# cpu.net
KiCad netlist of a schematic drawn in Altium Designer
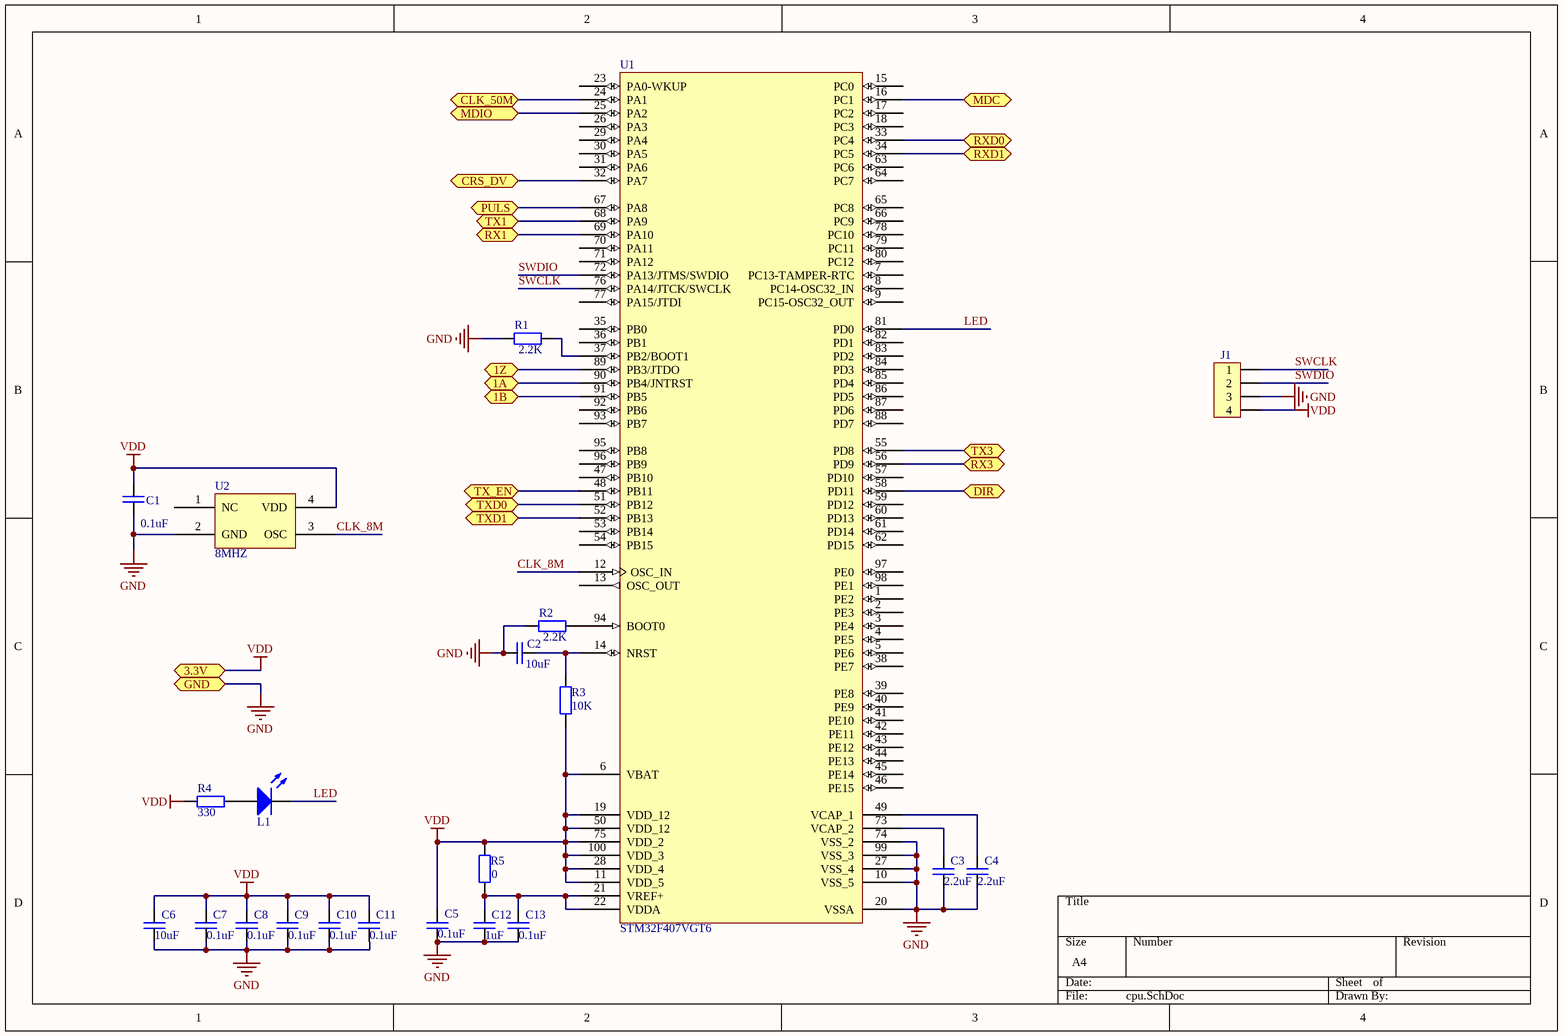
[diagram p0: cpu.SchDoc]

(export (version "E")
  (design (tool "Eeschema 10.0.6"))
  (components
    (comp (ref "C1")
      (value "0.1uF")
      (footprint "CAP-0805")
      (fields (field (name "Comment") "CAP"))
      (libsource (lib "Schlib1") (part "CAP"))
    )
    (comp (ref "C2")
      (value "10uF")
      (footprint "CAP-0805")
      (fields (field (name "Comment") "CAP"))
      (libsource (lib "Schlib1") (part "CAP"))
    )
    (comp (ref "C3")
      (value "2.2uF")
      (footprint "CAP-0805")
      (fields (field (name "Comment") "CAP"))
      (libsource (lib "Schlib1") (part "CAP"))
    )
    (comp (ref "C4")
      (value "2.2uF")
      (footprint "CAP-0805")
      (fields (field (name "Comment") "CAP"))
      (libsource (lib "Schlib1") (part "CAP"))
    )
    (comp (ref "C5")
      (value "0.1uF")
      (footprint "CAP-0805")
      (fields (field (name "Comment") "CAP"))
      (libsource (lib "Schlib1") (part "CAP"))
    )
    (comp (ref "C6")
      (value "10uF")
      (footprint "CAP-0805")
      (fields (field (name "Comment") "CAP"))
      (libsource (lib "Schlib1") (part "CAP"))
    )
    (comp (ref "C7")
      (value "0.1uF")
      (footprint "CAP-0805")
      (fields (field (name "Comment") "CAP"))
      (libsource (lib "Schlib1") (part "CAP"))
    )
    (comp (ref "C8")
      (value "0.1uF")
      (footprint "CAP-0805")
      (fields (field (name "Comment") "CAP"))
      (libsource (lib "Schlib1") (part "CAP"))
    )
    (comp (ref "C9")
      (value "0.1uF")
      (footprint "CAP-0805")
      (fields (field (name "Comment") "CAP"))
      (libsource (lib "Schlib1") (part "CAP"))
    )
    (comp (ref "C10")
      (value "0.1uF")
      (footprint "CAP-0805")
      (fields (field (name "Comment") "CAP"))
      (libsource (lib "Schlib1") (part "CAP"))
    )
    (comp (ref "C11")
      (value "0.1uF")
      (footprint "CAP-0805")
      (fields (field (name "Comment") "CAP"))
      (libsource (lib "Schlib1") (part "CAP"))
    )
    (comp (ref "C12")
      (value "1uF")
      (footprint "CAP-0805")
      (fields (field (name "Comment") "CAP"))
      (libsource (lib "Schlib1") (part "CAP"))
    )
    (comp (ref "C13")
      (value "0.1uF")
      (footprint "CAP-0805")
      (fields (field (name "Comment") "CAP"))
      (libsource (lib "Schlib1") (part "CAP"))
    )
    (comp (ref "J1") (value "HDR1*4") (footprint "HDR1*4") (libsource (lib "Schlib1") (part "HDR1*4")))
    (comp (ref "L1") (value "LED") (footprint "LED-0805") (libsource (lib "Schlib1") (part "LED")))
    (comp (ref "R1")
      (value "2.2K")
      (footprint "RES-0805")
      (fields (field (name "Comment") "RES"))
      (libsource (lib "Schlib1") (part "RES"))
    )
    (comp (ref "R2")
      (value "2.2K")
      (footprint "RES-0805")
      (fields (field (name "Comment") "RES"))
      (libsource (lib "Schlib1") (part "RES"))
    )
    (comp (ref "R3")
      (value "10K")
      (footprint "RES-0805")
      (fields (field (name "Comment") "RES"))
      (libsource (lib "") (part "RES_2"))
    )
    (comp (ref "R4")
      (value "330")
      (footprint "RES-0805")
      (fields (field (name "Comment") "RES"))
      (libsource (lib "") (part "RES_3"))
    )
    (comp (ref "R5")
      (value "0")
      (footprint "RES-0805")
      (fields (field (name "Comment") "RES"))
      (libsource (lib "") (part "RES_1"))
    )
    (comp (ref "U1")
      (value "STM32F407VGT6")
      (footprint "STM32-LQFP100")
      (libsource (lib "Schlib1") (part "STM32F407VGT6"))
    )
    (comp (ref "U2") (value "8MHZ") (footprint "OSC_S") (libsource (lib "Schlib1") (part "OSC")))
  )
  (nets
    (net (code "1") (name "/1A") (class "Default")
      (node (ref "U1") (pin "90") (pinfunction "PB4/JNTRST_90") (pintype "bidirectional"))
    )
    (net (code "2") (name "/1B") (class "Default")
      (node (ref "U1") (pin "91") (pinfunction "PB5_91") (pintype "bidirectional"))
    )
    (net (code "3") (name "/1Z") (class "Default")
      (node (ref "U1") (pin "89") (pinfunction "PB3/JTDO_89") (pintype "bidirectional"))
    )
    (net (code "4") (name "/CLK_8M") (class "Default")
      (node (ref "U1") (pin "12") (pinfunction "OSC_IN_12") (pintype "input"))
      (node (ref "U2") (pin "3") (pinfunction "OSC_3") (pintype "passive"))
    )
    (net (code "5") (name "/CLK_50M") (class "Default")
      (node (ref "U1") (pin "24") (pinfunction "PA1_24") (pintype "bidirectional"))
    )
    (net (code "6") (name "/CRS_DV") (class "Default")
      (node (ref "U1") (pin "32") (pinfunction "PA7_32") (pintype "bidirectional"))
    )
    (net (code "7") (name "/DIR") (class "Default")
      (node (ref "U1") (pin "58") (pinfunction "PD11_58") (pintype "bidirectional"))
    )
    (net (code "8") (name "/LED") (class "Default")
      (node (ref "L1") (pin "2") (pintype "passive"))
      (node (ref "U1") (pin "81") (pinfunction "PD0_81") (pintype "bidirectional"))
    )
    (net (code "9") (name "/MDC") (class "Default")
      (node (ref "U1") (pin "16") (pinfunction "PC1_16") (pintype "bidirectional"))
    )
    (net (code "10") (name "/MDIO") (class "Default")
      (node (ref "U1") (pin "25") (pinfunction "PA2_25") (pintype "bidirectional"))
    )
    (net (code "11") (name "/PULS") (class "Default")
      (node (ref "U1") (pin "67") (pinfunction "PA8_67") (pintype "bidirectional"))
    )
    (net (code "12") (name "/RX1") (class "Default")
      (node (ref "U1") (pin "69") (pinfunction "PA10_69") (pintype "bidirectional"))
    )
    (net (code "13") (name "/RX3") (class "Default")
      (node (ref "U1") (pin "56") (pinfunction "PD9_56") (pintype "bidirectional"))
    )
    (net (code "14") (name "/RXD0") (class "Default")
      (node (ref "U1") (pin "33") (pinfunction "PC4_33") (pintype "bidirectional"))
    )
    (net (code "15") (name "/RXD1") (class "Default")
      (node (ref "U1") (pin "34") (pinfunction "PC5_34") (pintype "bidirectional"))
    )
    (net (code "16") (name "/SWCLK") (class "Default")
      (node (ref "J1") (pin "1") (pinfunction "1_1") (pintype "passive"))
      (node (ref "U1") (pin "76") (pinfunction "PA14/JTCK/SWCLK_76") (pintype "bidirectional"))
    )
    (net (code "17") (name "/SWDIO") (class "Default")
      (node (ref "J1") (pin "2") (pinfunction "2_2") (pintype "passive"))
      (node (ref "U1") (pin "72") (pinfunction "PA13/JTMS/SWDIO_72") (pintype "bidirectional"))
    )
    (net (code "18") (name "/TX1") (class "Default")
      (node (ref "U1") (pin "68") (pinfunction "PA9_68") (pintype "bidirectional"))
    )
    (net (code "19") (name "/TX3") (class "Default")
      (node (ref "U1") (pin "55") (pinfunction "PD8_55") (pintype "bidirectional"))
    )
    (net (code "20") (name "/TXD0") (class "Default")
      (node (ref "U1") (pin "51") (pinfunction "PB12_51") (pintype "bidirectional"))
    )
    (net (code "21") (name "/TXD1") (class "Default")
      (node (ref "U1") (pin "52") (pinfunction "PB13_52") (pintype "bidirectional"))
    )
    (net (code "22") (name "/TX_EN") (class "Default")
      (node (ref "U1") (pin "48") (pinfunction "PB11_48") (pintype "bidirectional"))
    )
    (net (code "23") (name "GND") (class "Default")
      (node (ref "C1") (pin "1") (pintype "passive"))
      (node (ref "C10") (pin "1") (pintype "passive"))
      (node (ref "C11") (pin "1") (pintype "passive"))
      (node (ref "C12") (pin "1") (pintype "passive"))
      (node (ref "C13") (pin "1") (pintype "passive"))
      (node (ref "C2") (pin "1") (pintype "passive"))
      (node (ref "C3") (pin "1") (pintype "passive"))
      (node (ref "C4") (pin "1") (pintype "passive"))
      (node (ref "C5") (pin "1") (pintype "passive"))
      (node (ref "C6") (pin "1") (pintype "passive"))
      (node (ref "C7") (pin "1") (pintype "passive"))
      (node (ref "C8") (pin "1") (pintype "passive"))
      (node (ref "C9") (pin "1") (pintype "passive"))
      (node (ref "J1") (pin "3") (pinfunction "3_3") (pintype "passive"))
      (node (ref "R1") (pin "2") (pintype "passive"))
      (node (ref "R2") (pin "2") (pintype "passive"))
      (node (ref "U1") (pin "10") (pinfunction "VSS_5_10") (pintype "power_in"))
      (node (ref "U1") (pin "20") (pinfunction "VSSA_20") (pintype "power_in"))
      (node (ref "U1") (pin "27") (pinfunction "VSS_4_27") (pintype "power_in"))
      (node (ref "U1") (pin "74") (pinfunction "VSS_2_74") (pintype "passive"))
      (node (ref "U1") (pin "99") (pinfunction "VSS_3_99") (pintype "power_in"))
      (node (ref "U2") (pin "2") (pinfunction "GND_2") (pintype "passive"))
    )
    (net (code "24") (name "Net-(L1-Pad1)") (class "Default")
      (node (ref "L1") (pin "1") (pintype "passive"))
      (node (ref "R4") (pin "2") (pintype "passive"))
    )
    (net (code "25") (name "Net-(U1-BOOT0)") (class "Default")
      (node (ref "R2") (pin "1") (pintype "passive"))
      (node (ref "U1") (pin "94") (pinfunction "BOOT0_94") (pintype "input"))
    )
    (net (code "26") (name "Net-(U1-NRST)") (class "Default")
      (node (ref "C2") (pin "2") (pintype "passive"))
      (node (ref "R3") (pin "1") (pintype "passive"))
      (node (ref "U1") (pin "14") (pinfunction "NRST_14") (pintype "bidirectional"))
    )
    (net (code "27") (name "Net-(U1-PB2{slash}BOOT1)") (class "Default")
      (node (ref "R1") (pin "1") (pintype "passive"))
      (node (ref "U1") (pin "37") (pinfunction "PB2/BOOT1_37") (pintype "bidirectional"))
    )
    (net (code "28") (name "Net-(U1-VCAP_1)") (class "Default")
      (node (ref "C4") (pin "2") (pintype "passive"))
      (node (ref "U1") (pin "49") (pinfunction "VCAP_1_49") (pintype "power_in"))
    )
    (net (code "29") (name "Net-(U1-VCAP_2)") (class "Default")
      (node (ref "C3") (pin "2") (pintype "passive"))
      (node (ref "U1") (pin "73") (pinfunction "VCAP_2_73") (pintype "power_in"))
    )
    (net (code "30") (name "Net-(U1-VDDA)") (class "Default")
      (node (ref "C12") (pin "2") (pintype "passive"))
      (node (ref "C13") (pin "2") (pintype "passive"))
      (node (ref "R5") (pin "1") (pintype "passive"))
      (node (ref "U1") (pin "21") (pinfunction "VREF+_21") (pintype "power_in"))
      (node (ref "U1") (pin "22") (pinfunction "VDDA_22") (pintype "power_in"))
    )
    (net (code "31") (name "VDD") (class "Default")
      (node (ref "C1") (pin "2") (pintype "passive"))
      (node (ref "C10") (pin "2") (pintype "passive"))
      (node (ref "C11") (pin "2") (pintype "passive"))
      (node (ref "C5") (pin "2") (pintype "passive"))
      (node (ref "C6") (pin "2") (pintype "passive"))
      (node (ref "C7") (pin "2") (pintype "passive"))
      (node (ref "C8") (pin "2") (pintype "passive"))
      (node (ref "C9") (pin "2") (pintype "passive"))
      (node (ref "J1") (pin "4") (pinfunction "4_4") (pintype "passive"))
      (node (ref "R3") (pin "2") (pintype "passive"))
      (node (ref "R4") (pin "1") (pintype "passive"))
      (node (ref "R5") (pin "2") (pintype "passive"))
      (node (ref "U1") (pin "100") (pinfunction "VDD_3_100") (pintype "power_in"))
      (node (ref "U1") (pin "11") (pinfunction "VDD_5_11") (pintype "power_in"))
      (node (ref "U1") (pin "19") (pinfunction "VDD_12_19") (pintype "passive"))
      (node (ref "U1") (pin "28") (pinfunction "VDD_4_28") (pintype "power_in"))
      (node (ref "U1") (pin "50") (pinfunction "VDD_12_50") (pintype "power_in"))
      (node (ref "U1") (pin "6") (pinfunction "VBAT_6") (pintype "power_in"))
      (node (ref "U1") (pin "75") (pinfunction "VDD_2_75") (pintype "power_in"))
      (node (ref "U2") (pin "4") (pinfunction "VDD_4") (pintype "passive"))
    )
    (net (code "32") (name "unconnected-(U1-OSC_OUT-Pad13)") (class "Default")
      (node (ref "U1") (pin "13") (pinfunction "OSC_OUT_13") (pintype "output"))
    )
    (net (code "33") (name "unconnected-(U1-PA0-WKUP-Pad23)") (class "Default")
      (node (ref "U1") (pin "23") (pinfunction "PA0-WKUP_23") (pintype "bidirectional"))
    )
    (net (code "34") (name "unconnected-(U1-PA3-Pad26)") (class "Default")
      (node (ref "U1") (pin "26") (pinfunction "PA3_26") (pintype "bidirectional"))
    )
    (net (code "35") (name "unconnected-(U1-PA4-Pad29)") (class "Default")
      (node (ref "U1") (pin "29") (pinfunction "PA4_29") (pintype "bidirectional"))
    )
    (net (code "36") (name "unconnected-(U1-PA5-Pad30)") (class "Default")
      (node (ref "U1") (pin "30") (pinfunction "PA5_30") (pintype "bidirectional"))
    )
    (net (code "37") (name "unconnected-(U1-PA6-Pad31)") (class "Default")
      (node (ref "U1") (pin "31") (pinfunction "PA6_31") (pintype "bidirectional"))
    )
    (net (code "38") (name "unconnected-(U1-PA11-Pad70)") (class "Default")
      (node (ref "U1") (pin "70") (pinfunction "PA11_70") (pintype "bidirectional"))
    )
    (net (code "39") (name "unconnected-(U1-PA12-Pad71)") (class "Default")
      (node (ref "U1") (pin "71") (pinfunction "PA12_71") (pintype "bidirectional"))
    )
    (net (code "40") (name "unconnected-(U1-PA15{slash}JTDI-Pad77)") (class "Default")
      (node (ref "U1") (pin "77") (pinfunction "PA15/JTDI_77") (pintype "bidirectional"))
    )
    (net (code "41") (name "unconnected-(U1-PB0-Pad35)") (class "Default")
      (node (ref "U1") (pin "35") (pinfunction "PB0_35") (pintype "bidirectional"))
    )
    (net (code "42") (name "unconnected-(U1-PB1-Pad36)") (class "Default")
      (node (ref "U1") (pin "36") (pinfunction "PB1_36") (pintype "bidirectional"))
    )
    (net (code "43") (name "unconnected-(U1-PB6-Pad92)") (class "Default")
      (node (ref "U1") (pin "92") (pinfunction "PB6_92") (pintype "bidirectional"))
    )
    (net (code "44") (name "unconnected-(U1-PB7-Pad93)") (class "Default")
      (node (ref "U1") (pin "93") (pinfunction "PB7_93") (pintype "bidirectional"))
    )
    (net (code "45") (name "unconnected-(U1-PB8-Pad95)") (class "Default")
      (node (ref "U1") (pin "95") (pinfunction "PB8_95") (pintype "bidirectional"))
    )
    (net (code "46") (name "unconnected-(U1-PB9-Pad96)") (class "Default")
      (node (ref "U1") (pin "96") (pinfunction "PB9_96") (pintype "bidirectional"))
    )
    (net (code "47") (name "unconnected-(U1-PB10-Pad47)") (class "Default")
      (node (ref "U1") (pin "47") (pinfunction "PB10_47") (pintype "bidirectional"))
    )
    (net (code "48") (name "unconnected-(U1-PB14-Pad53)") (class "Default")
      (node (ref "U1") (pin "53") (pinfunction "PB14_53") (pintype "bidirectional"))
    )
    (net (code "49") (name "unconnected-(U1-PB15-Pad54)") (class "Default")
      (node (ref "U1") (pin "54") (pinfunction "PB15_54") (pintype "bidirectional"))
    )
    (net (code "50") (name "unconnected-(U1-PC0-Pad15)") (class "Default")
      (node (ref "U1") (pin "15") (pinfunction "PC0_15") (pintype "bidirectional"))
    )
    (net (code "51") (name "unconnected-(U1-PC2-Pad17)") (class "Default")
      (node (ref "U1") (pin "17") (pinfunction "PC2_17") (pintype "bidirectional"))
    )
    (net (code "52") (name "unconnected-(U1-PC3-Pad18)") (class "Default")
      (node (ref "U1") (pin "18") (pinfunction "PC3_18") (pintype "bidirectional"))
    )
    (net (code "53") (name "unconnected-(U1-PC6-Pad63)") (class "Default")
      (node (ref "U1") (pin "63") (pinfunction "PC6_63") (pintype "bidirectional"))
    )
    (net (code "54") (name "unconnected-(U1-PC7-Pad64)") (class "Default")
      (node (ref "U1") (pin "64") (pinfunction "PC7_64") (pintype "bidirectional"))
    )
    (net (code "55") (name "unconnected-(U1-PC8-Pad65)") (class "Default")
      (node (ref "U1") (pin "65") (pinfunction "PC8_65") (pintype "bidirectional"))
    )
    (net (code "56") (name "unconnected-(U1-PC9-Pad66)") (class "Default")
      (node (ref "U1") (pin "66") (pinfunction "PC9_66") (pintype "bidirectional"))
    )
    (net (code "57") (name "unconnected-(U1-PC10-Pad78)") (class "Default")
      (node (ref "U1") (pin "78") (pinfunction "PC10_78") (pintype "bidirectional"))
    )
    (net (code "58") (name "unconnected-(U1-PC11-Pad79)") (class "Default")
      (node (ref "U1") (pin "79") (pinfunction "PC11_79") (pintype "bidirectional"))
    )
    (net (code "59") (name "unconnected-(U1-PC12-Pad80)") (class "Default")
      (node (ref "U1") (pin "80") (pinfunction "PC12_80") (pintype "bidirectional"))
    )
    (net (code "60") (name "unconnected-(U1-PC13-TAMPER-RTC-Pad7)") (class "Default")
      (node (ref "U1") (pin "7") (pinfunction "PC13-TAMPER-RTC_7") (pintype "bidirectional"))
    )
    (net (code "61") (name "unconnected-(U1-PC14-OSC32_IN-Pad8)") (class "Default")
      (node (ref "U1") (pin "8") (pinfunction "PC14-OSC32_IN_8") (pintype "bidirectional"))
    )
    (net (code "62") (name "unconnected-(U1-PC15-OSC32_OUT-Pad9)") (class "Default")
      (node (ref "U1") (pin "9") (pinfunction "PC15-OSC32_OUT_9") (pintype "bidirectional"))
    )
    (net (code "63") (name "unconnected-(U1-PD1-Pad82)") (class "Default")
      (node (ref "U1") (pin "82") (pinfunction "PD1_82") (pintype "bidirectional"))
    )
    (net (code "64") (name "unconnected-(U1-PD2-Pad83)") (class "Default")
      (node (ref "U1") (pin "83") (pinfunction "PD2_83") (pintype "bidirectional"))
    )
    (net (code "65") (name "unconnected-(U1-PD3-Pad84)") (class "Default")
      (node (ref "U1") (pin "84") (pinfunction "PD3_84") (pintype "bidirectional"))
    )
    (net (code "66") (name "unconnected-(U1-PD4-Pad85)") (class "Default")
      (node (ref "U1") (pin "85") (pinfunction "PD4_85") (pintype "bidirectional"))
    )
    (net (code "67") (name "unconnected-(U1-PD5-Pad86)") (class "Default")
      (node (ref "U1") (pin "86") (pinfunction "PD5_86") (pintype "bidirectional"))
    )
    (net (code "68") (name "unconnected-(U1-PD6-Pad87)") (class "Default")
      (node (ref "U1") (pin "87") (pinfunction "PD6_87") (pintype "bidirectional"))
    )
    (net (code "69") (name "unconnected-(U1-PD7-Pad88)") (class "Default")
      (node (ref "U1") (pin "88") (pinfunction "PD7_88") (pintype "bidirectional"))
    )
    (net (code "70") (name "unconnected-(U1-PD10-Pad57)") (class "Default")
      (node (ref "U1") (pin "57") (pinfunction "PD10_57") (pintype "bidirectional"))
    )
    (net (code "71") (name "unconnected-(U1-PD12-Pad59)") (class "Default")
      (node (ref "U1") (pin "59") (pinfunction "PD12_59") (pintype "bidirectional"))
    )
    (net (code "72") (name "unconnected-(U1-PD13-Pad60)") (class "Default")
      (node (ref "U1") (pin "60") (pinfunction "PD13_60") (pintype "bidirectional"))
    )
    (net (code "73") (name "unconnected-(U1-PD14-Pad61)") (class "Default")
      (node (ref "U1") (pin "61") (pinfunction "PD14_61") (pintype "bidirectional"))
    )
    (net (code "74") (name "unconnected-(U1-PD15-Pad62)") (class "Default")
      (node (ref "U1") (pin "62") (pinfunction "PD15_62") (pintype "bidirectional"))
    )
    (net (code "75") (name "unconnected-(U1-PE0-Pad97)") (class "Default")
      (node (ref "U1") (pin "97") (pinfunction "PE0_97") (pintype "bidirectional"))
    )
    (net (code "76") (name "unconnected-(U1-PE1-Pad98)") (class "Default")
      (node (ref "U1") (pin "98") (pinfunction "PE1_98") (pintype "bidirectional"))
    )
    (net (code "77") (name "unconnected-(U1-PE2-Pad1)") (class "Default")
      (node (ref "U1") (pin "1") (pinfunction "PE2_1") (pintype "bidirectional"))
    )
    (net (code "78") (name "unconnected-(U1-PE3-Pad2)") (class "Default")
      (node (ref "U1") (pin "2") (pinfunction "PE3_2") (pintype "bidirectional"))
    )
    (net (code "79") (name "unconnected-(U1-PE4-Pad3)") (class "Default")
      (node (ref "U1") (pin "3") (pinfunction "PE4_3") (pintype "bidirectional"))
    )
    (net (code "80") (name "unconnected-(U1-PE5-Pad4)") (class "Default")
      (node (ref "U1") (pin "4") (pinfunction "PE5_4") (pintype "bidirectional"))
    )
    (net (code "81") (name "unconnected-(U1-PE6-Pad5)") (class "Default")
      (node (ref "U1") (pin "5") (pinfunction "PE6_5") (pintype "bidirectional"))
    )
    (net (code "82") (name "unconnected-(U1-PE7-Pad38)") (class "Default")
      (node (ref "U1") (pin "38") (pinfunction "PE7_38") (pintype "bidirectional"))
    )
    (net (code "83") (name "unconnected-(U1-PE8-Pad39)") (class "Default")
      (node (ref "U1") (pin "39") (pinfunction "PE8_39") (pintype "bidirectional"))
    )
    (net (code "84") (name "unconnected-(U1-PE9-Pad40)") (class "Default")
      (node (ref "U1") (pin "40") (pinfunction "PE9_40") (pintype "bidirectional"))
    )
    (net (code "85") (name "unconnected-(U1-PE10-Pad41)") (class "Default")
      (node (ref "U1") (pin "41") (pinfunction "PE10_41") (pintype "bidirectional"))
    )
    (net (code "86") (name "unconnected-(U1-PE11-Pad42)") (class "Default")
      (node (ref "U1") (pin "42") (pinfunction "PE11_42") (pintype "bidirectional"))
    )
    (net (code "87") (name "unconnected-(U1-PE12-Pad43)") (class "Default")
      (node (ref "U1") (pin "43") (pinfunction "PE12_43") (pintype "bidirectional"))
    )
    (net (code "88") (name "unconnected-(U1-PE13-Pad44)") (class "Default")
      (node (ref "U1") (pin "44") (pinfunction "PE13_44") (pintype "bidirectional"))
    )
    (net (code "89") (name "unconnected-(U1-PE14-Pad45)") (class "Default")
      (node (ref "U1") (pin "45") (pinfunction "PE14_45") (pintype "bidirectional"))
    )
    (net (code "90") (name "unconnected-(U1-PE15-Pad46)") (class "Default")
      (node (ref "U1") (pin "46") (pinfunction "PE15_46") (pintype "bidirectional"))
    )
    (net (code "91") (name "unconnected-(U2-NC-Pad1)") (class "Default")
      (node (ref "U2") (pin "1") (pinfunction "NC_1") (pintype "passive"))
    )
  )
)
